# HF_Receiver.net
KiCad netlist of a schematic drawn in EAGLE
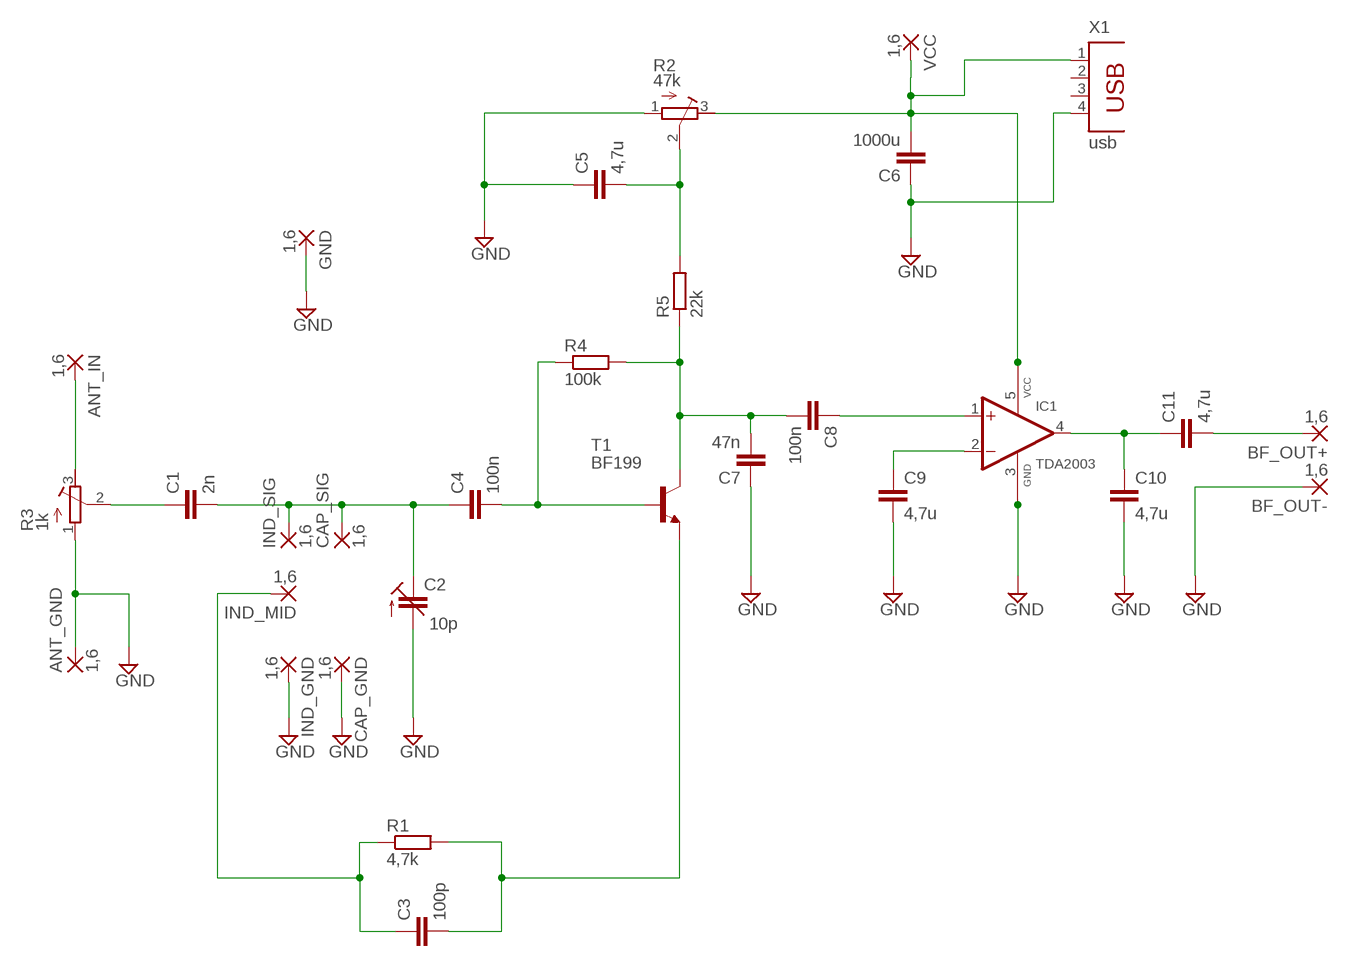
[diagram p0: schematic, sheet 1]

(export (version "E")
  (design (tool "Eeschema 10.0.6"))
  (components
    (comp (ref "ANT_GND")
      (value "1,6")
      (footprint "eagle-import:1,6_0,9")
      (libsource (lib "eagle-import") (part "1,6/0,9"))
    )
    (comp (ref "ANT_IN")
      (value "1,6")
      (footprint "eagle-import:1,6_0,9")
      (libsource (lib "eagle-import") (part "1,6/0,9"))
    )
    (comp (ref "BF_OUT+")
      (value "1,6")
      (footprint "eagle-import:1,6_0,9")
      (libsource (lib "eagle-import") (part "1,6/0,9"))
    )
    (comp (ref "BF_OUT-")
      (value "1,6")
      (footprint "eagle-import:1,6_0,9")
      (libsource (lib "eagle-import") (part "1,6/0,9"))
    )
    (comp (ref "C1")
      (value "2n")
      (footprint "eagle-import:C075-032X103")
      (libsource (lib "eagle-import") (part "C-EU075-032X103"))
    )
    (comp (ref "C2")
      (value "10p")
      (footprint "eagle-import:CTRIM808-BC")
      (libsource (lib "eagle-import") (part "C-TRIMM808"))
    )
    (comp (ref "C3")
      (value "100p")
      (footprint "eagle-import:C075-032X103")
      (libsource (lib "eagle-import") (part "C-EU075-032X103"))
    )
    (comp (ref "C4")
      (value "100n")
      (footprint "eagle-import:C075-032X103")
      (libsource (lib "eagle-import") (part "C-EU075-032X103"))
    )
    (comp (ref "C5")
      (value "4,7u")
      (footprint "eagle-import:C075-032X103")
      (libsource (lib "eagle-import") (part "C-EU075-032X103"))
    )
    (comp (ref "C6")
      (value "1000u")
      (footprint "eagle-import:C075-032X103")
      (libsource (lib "eagle-import") (part "C-EU075-032X103"))
    )
    (comp (ref "C7")
      (value "47n")
      (footprint "eagle-import:C075-032X103")
      (libsource (lib "eagle-import") (part "C-EU075-032X103"))
    )
    (comp (ref "C8")
      (value "100n")
      (footprint "eagle-import:C075-032X103")
      (libsource (lib "eagle-import") (part "C-EU075-032X103"))
    )
    (comp (ref "C9")
      (value "4,7u")
      (footprint "eagle-import:C075-032X103")
      (libsource (lib "eagle-import") (part "C-EU075-032X103"))
    )
    (comp (ref "C10")
      (value "4,7u")
      (footprint "eagle-import:C075-032X103")
      (libsource (lib "eagle-import") (part "C-EU075-032X103"))
    )
    (comp (ref "C11")
      (value "4,7u")
      (footprint "eagle-import:C075-032X103")
      (libsource (lib "eagle-import") (part "C-EU075-032X103"))
    )
    (comp (ref "CAP_GND")
      (value "1,6")
      (footprint "eagle-import:1,6_0,9")
      (libsource (lib "eagle-import") (part "1,6/0,9"))
    )
    (comp (ref "CAP_SIG")
      (value "1,6")
      (footprint "eagle-import:1,6_0,9")
      (libsource (lib "eagle-import") (part "1,6/0,9"))
    )
    (comp (ref "GND")
      (value "1,6")
      (footprint "eagle-import:1,6_0,9")
      (libsource (lib "eagle-import") (part "1,6/0,9"))
    )
    (comp (ref "IC1")
      (value "TDA2003")
      (footprint "eagle-import:PENTAWATT-V")
      (libsource (lib "eagle-import") (part "TDA2003"))
    )
    (comp (ref "IND_GND")
      (value "1,6")
      (footprint "eagle-import:1,6_0,9")
      (libsource (lib "eagle-import") (part "1,6/0,9"))
    )
    (comp (ref "IND_MID")
      (value "1,6")
      (footprint "eagle-import:1,6_0,9")
      (libsource (lib "eagle-import") (part "1,6/0,9"))
    )
    (comp (ref "IND_SIG")
      (value "1,6")
      (footprint "eagle-import:1,6_0,9")
      (libsource (lib "eagle-import") (part "1,6/0,9"))
    )
    (comp (ref "R1")
      (value "4,7k")
      (footprint "eagle-import:0207_10")
      (libsource (lib "eagle-import") (part "R-EU_0207/10"))
    )
    (comp (ref "R2")
      (value "47k")
      (footprint "eagle-import:RTRIM3339P")
      (libsource (lib "eagle-import") (part "R-TRIMM3339P"))
    )
    (comp (ref "R3")
      (value "1k")
      (footprint "eagle-import:RTRIM3339P")
      (libsource (lib "eagle-import") (part "R-TRIMM3339P"))
    )
    (comp (ref "R4")
      (value "100k")
      (footprint "eagle-import:0207_10")
      (libsource (lib "eagle-import") (part "R-EU_0207/10"))
    )
    (comp (ref "R5")
      (value "22k")
      (footprint "eagle-import:0207_10")
      (libsource (lib "eagle-import") (part "R-EU_0207/10"))
    )
    (comp (ref "T1")
      (value "BF199")
      (footprint "eagle-import:TO92")
      (libsource (lib "eagle-import") (part "BF199"))
    )
    (comp (ref "VCC")
      (value "1,6")
      (footprint "eagle-import:1,6_0,9")
      (libsource (lib "eagle-import") (part "1,6/0,9"))
    )
    (comp (ref "X1")
      (value "usb")
      (footprint "eagle-import:PN87520")
      (libsource (lib "eagle-import") (part "PN87520"))
    )
  )
  (nets
    (net (code "1") (name "GND") (class "Default")
      (node (ref "ANT_GND") (pin "1") (pinfunction "P_1") (pintype "passive"))
      (node (ref "BF_OUT-") (pin "1") (pinfunction "P_1") (pintype "passive"))
      (node (ref "C10") (pin "2") (pinfunction "2_2") (pintype "passive"))
      (node (ref "C2") (pin "2") (pinfunction "A_2") (pintype "passive"))
      (node (ref "C5") (pin "1") (pinfunction "1_1") (pintype "passive"))
      (node (ref "C6") (pin "1") (pinfunction "1_1") (pintype "passive"))
      (node (ref "C7") (pin "1") (pinfunction "1_1") (pintype "passive"))
      (node (ref "C9") (pin "2") (pinfunction "2_2") (pintype "passive"))
      (node (ref "CAP_GND") (pin "1") (pinfunction "P_1") (pintype "passive"))
      (node (ref "GND") (pin "1") (pinfunction "P_1") (pintype "passive"))
      (node (ref "IC1") (pin "3") (pinfunction "GND_3") (pintype "power_in"))
      (node (ref "IND_GND") (pin "1") (pinfunction "P_1") (pintype "passive"))
      (node (ref "R2") (pin "1") (pinfunction "A_1") (pintype "passive"))
      (node (ref "R3") (pin "1") (pinfunction "A_1") (pintype "passive"))
      (node (ref "X1") (pin "4") (pinfunction "4_4") (pintype "passive"))
    )
    (net (code "2") (name "Net-(ANT_IN-P)") (class "Default")
      (node (ref "ANT_IN") (pin "1") (pinfunction "P_1") (pintype "passive"))
      (node (ref "R3") (pin "3") (pinfunction "E_3") (pintype "passive"))
    )
    (net (code "3") (name "Net-(BF_OUT+-P)") (class "Default")
      (node (ref "BF_OUT+") (pin "1") (pinfunction "P_1") (pintype "passive"))
      (node (ref "C11") (pin "2") (pinfunction "2_2") (pintype "passive"))
    )
    (net (code "4") (name "Net-(C2-E)") (class "Default")
      (node (ref "C1") (pin "2") (pinfunction "2_2") (pintype "passive"))
      (node (ref "C2") (pin "1") (pinfunction "E_1") (pintype "passive"))
      (node (ref "C4") (pin "1") (pinfunction "1_1") (pintype "passive"))
      (node (ref "CAP_SIG") (pin "1") (pinfunction "P_1") (pintype "passive"))
      (node (ref "IND_SIG") (pin "1") (pinfunction "P_1") (pintype "passive"))
    )
    (net (code "5") (name "Net-(IC1-+IN)") (class "Default")
      (node (ref "C8") (pin "1") (pinfunction "1_1") (pintype "passive"))
      (node (ref "IC1") (pin "1") (pinfunction "+IN_1") (pintype "input"))
    )
    (net (code "6") (name "Net-(IC1--IN)") (class "Default")
      (node (ref "C9") (pin "1") (pinfunction "1_1") (pintype "passive"))
      (node (ref "IC1") (pin "2") (pinfunction "-IN_2") (pintype "input"))
    )
    (net (code "7") (name "Net-(IC1-OUT)") (class "Default")
      (node (ref "C10") (pin "1") (pinfunction "1_1") (pintype "passive"))
      (node (ref "C11") (pin "1") (pinfunction "1_1") (pintype "passive"))
      (node (ref "IC1") (pin "4") (pinfunction "OUT_4") (pintype "output"))
    )
    (net (code "8") (name "Net-(IC1-VCC)") (class "Default")
      (node (ref "C6") (pin "2") (pinfunction "2_2") (pintype "passive"))
      (node (ref "IC1") (pin "5") (pinfunction "VCC_5") (pintype "power_in"))
      (node (ref "R2") (pin "3") (pinfunction "E_3") (pintype "passive"))
      (node (ref "VCC") (pin "1") (pinfunction "P_1") (pintype "passive"))
      (node (ref "X1") (pin "1") (pinfunction "1_1") (pintype "passive"))
    )
    (net (code "9") (name "Net-(IND_MID-P)") (class "Default")
      (node (ref "C3") (pin "1") (pinfunction "1_1") (pintype "passive"))
      (node (ref "IND_MID") (pin "1") (pinfunction "P_1") (pintype "passive"))
      (node (ref "R1") (pin "1") (pinfunction "1_1") (pintype "passive"))
    )
    (net (code "10") (name "Net-(R2-S)") (class "Default")
      (node (ref "C5") (pin "2") (pinfunction "2_2") (pintype "passive"))
      (node (ref "R2") (pin "2") (pinfunction "S_2") (pintype "passive"))
      (node (ref "R5") (pin "2") (pinfunction "2_2") (pintype "passive"))
    )
    (net (code "11") (name "Net-(R3-S)") (class "Default")
      (node (ref "C1") (pin "1") (pinfunction "1_1") (pintype "passive"))
      (node (ref "R3") (pin "2") (pinfunction "S_2") (pintype "passive"))
    )
    (net (code "12") (name "Net-(T1-B)") (class "Default")
      (node (ref "C4") (pin "2") (pinfunction "2_2") (pintype "passive"))
      (node (ref "R4") (pin "1") (pinfunction "1_1") (pintype "passive"))
      (node (ref "T1") (pin "1") (pinfunction "B_1") (pintype "passive"))
    )
    (net (code "13") (name "Net-(T1-C)") (class "Default")
      (node (ref "C7") (pin "2") (pinfunction "2_2") (pintype "passive"))
      (node (ref "C8") (pin "2") (pinfunction "2_2") (pintype "passive"))
      (node (ref "R4") (pin "2") (pinfunction "2_2") (pintype "passive"))
      (node (ref "R5") (pin "1") (pinfunction "1_1") (pintype "passive"))
      (node (ref "T1") (pin "3") (pinfunction "C_3") (pintype "passive"))
    )
    (net (code "14") (name "Net-(T1-E)") (class "Default")
      (node (ref "C3") (pin "2") (pinfunction "2_2") (pintype "passive"))
      (node (ref "R1") (pin "2") (pinfunction "2_2") (pintype "passive"))
      (node (ref "T1") (pin "2") (pinfunction "E_2") (pintype "passive"))
    )
    (net (code "15") (name "unconnected-(X1-Pad2)") (class "Default")
      (node (ref "X1") (pin "2") (pinfunction "2_2") (pintype "passive"))
    )
    (net (code "16") (name "unconnected-(X1-Pad3)") (class "Default")
      (node (ref "X1") (pin "3") (pinfunction "3_3") (pintype "passive"))
    )
  )
)
